# Blattdurchmesser.net
KiCad netlist of a schematic drawn in EAGLE
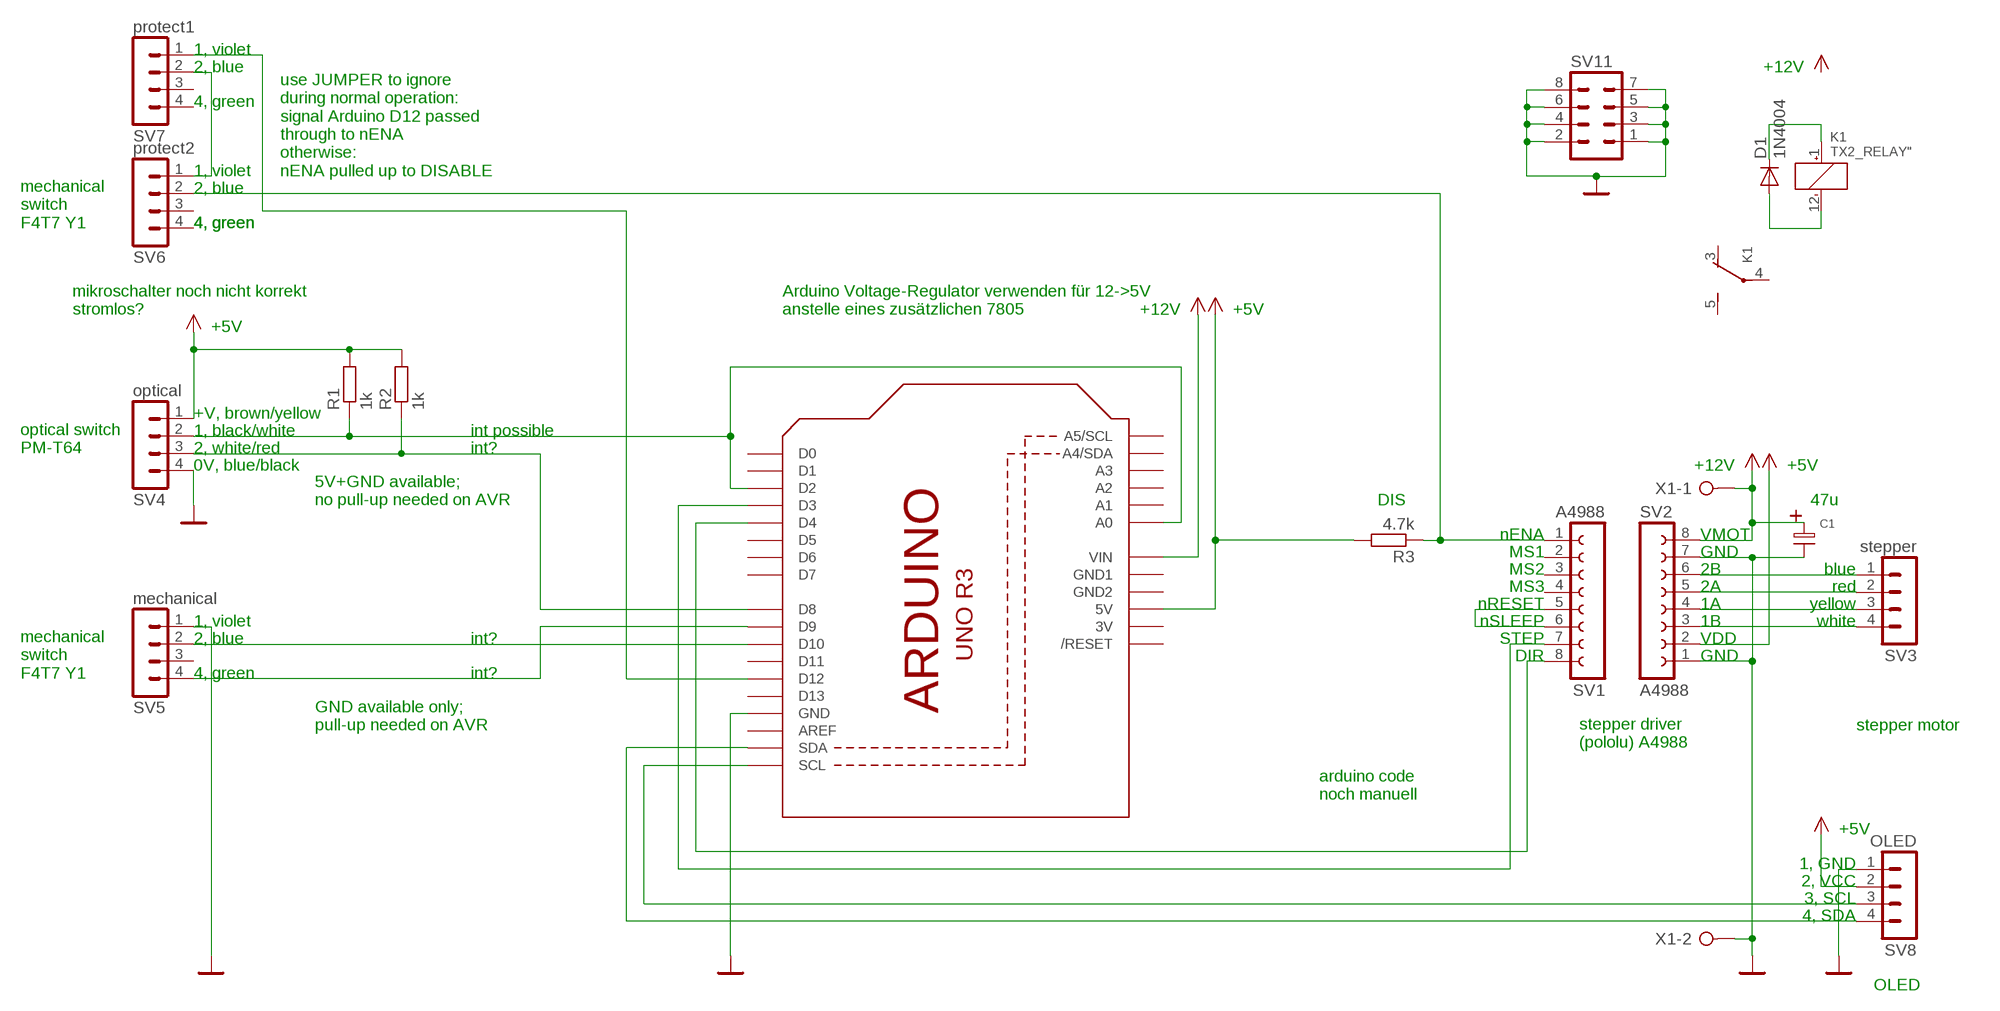
[diagram p0: schematic, sheet 1]

(export (version "E")
  (design (tool "Eeschema 10.0.6"))
  (components
    (comp (ref "C1")
      (value "R_ELKO_8.1")
      (footprint "eagle-import:R_ELK_8.1")
      (libsource (lib "eagle-import") (part "R_ELKO_8.1"))
    )
    (comp (ref "D1")
      (value "1N4004")
      (footprint "eagle-import:DO41-10")
      (libsource (lib "eagle-import") (part "1N4004"))
    )
    (comp (ref "K1")
      (value "TX2_RELAY\"")
      (footprint "eagle-import:TX2")
      (libsource (lib "eagle-import") (part "TX2_RELAY{dblquote}"))
    )
    (comp (ref "Q1")
      (value "ARDUINOR3-NOIOREF-NOTEXT")
      (footprint "eagle-import:ARDUINOR3-NOTEXT-NOIOREF")
      (libsource (lib "eagle-import") (part "ARDUINOR3-NOIOREF-NOTEXT"))
    )
    (comp (ref "R1")
      (value "1k")
      (footprint "eagle-import:0207_10")
      (libsource (lib "eagle-import") (part "R-EU_0207/10"))
    )
    (comp (ref "R2")
      (value "1k")
      (footprint "eagle-import:0207_10")
      (libsource (lib "eagle-import") (part "R-EU_0207/10"))
    )
    (comp (ref "R3")
      (value "4.7k")
      (footprint "eagle-import:0207_10")
      (libsource (lib "eagle-import") (part "R-EU_0207/10"))
    )
    (comp (ref "SV1")
      (value "A4988")
      (footprint "eagle-import:FE08")
      (libsource (lib "eagle-import") (part "FE08-1"))
    )
    (comp (ref "SV2")
      (value "A4988")
      (footprint "eagle-import:FE08")
      (libsource (lib "eagle-import") (part "FE08-1"))
    )
    (comp (ref "SV3")
      (value "stepper")
      (footprint "eagle-import:MA04-1")
      (libsource (lib "eagle-import") (part "MA04-1"))
    )
    (comp (ref "SV4")
      (value "optical")
      (footprint "eagle-import:MA04-1")
      (libsource (lib "eagle-import") (part "MA04-1"))
    )
    (comp (ref "SV5")
      (value "mechanical")
      (footprint "eagle-import:MA04-1")
      (libsource (lib "eagle-import") (part "MA04-1"))
    )
    (comp (ref "SV6")
      (value "protect2")
      (footprint "eagle-import:MA04-1")
      (libsource (lib "eagle-import") (part "MA04-1"))
    )
    (comp (ref "SV7")
      (value "protect1")
      (footprint "eagle-import:MA04-1")
      (libsource (lib "eagle-import") (part "MA04-1"))
    )
    (comp (ref "SV8")
      (value "OLED")
      (footprint "eagle-import:MA04-1")
      (libsource (lib "eagle-import") (part "MA04-1"))
    )
    (comp (ref "SV11")
      (value "MA04-2")
      (footprint "eagle-import:MA04-2")
      (libsource (lib "eagle-import") (part "MA04-2"))
    )
    (comp (ref "X1")
      (value "W237-02P")
      (footprint "eagle-import:W237-132")
      (libsource (lib "eagle-import") (part "W237-02P"))
    )
  )
  (nets
    (net (code "1") (name "+5V") (class "Default")
      (node (ref "Q1") (pin "5V") (pinfunction "5V_5V") (pintype "power_in"))
      (node (ref "R1") (pin "2") (pinfunction "2_2") (pintype "passive"))
      (node (ref "R2") (pin "2") (pinfunction "2_2") (pintype "passive"))
      (node (ref "R3") (pin "2") (pinfunction "2_2") (pintype "passive"))
      (node (ref "SV2") (pin "2") (pinfunction "2_2") (pintype "passive"))
      (node (ref "SV4") (pin "1") (pinfunction "1_1") (pintype "passive"))
      (node (ref "SV8") (pin "2") (pinfunction "2_2") (pintype "passive"))
    )
    (net (code "2") (name "+12V") (class "Default")
      (node (ref "C1") (pin "P") (pinfunction "P_P") (pintype "passive"))
      (node (ref "Q1") (pin "VIN") (pinfunction "VIN_VIN") (pintype "power_in"))
      (node (ref "SV2") (pin "8") (pinfunction "8_8") (pintype "passive"))
      (node (ref "X1") (pin "1") (pinfunction "KL_1") (pintype "passive"))
    )
    (net (code "3") (name "/3V") (class "Default")
      (node (ref "Q1") (pin "3V") (pinfunction "3V_3V") (pintype "power_in"))
    )
    (net (code "4") (name "/GND1") (class "Default")
      (node (ref "Q1") (pin "GND1") (pinfunction "GND1_GND1") (pintype "power_in"))
    )
    (net (code "5") (name "/GND2") (class "Default")
      (node (ref "Q1") (pin "GND2") (pinfunction "GND2_GND2") (pintype "power_in"))
    )
    (net (code "6") (name "GND") (class "Default")
      (node (ref "C1") (pin "N") (pinfunction "N_N") (pintype "passive"))
      (node (ref "Q1") (pin "GND") (pinfunction "GND_GND") (pintype "power_in"))
      (node (ref "SV11") (pin "1") (pinfunction "1_1") (pintype "passive"))
      (node (ref "SV11") (pin "2") (pinfunction "2_2") (pintype "passive"))
      (node (ref "SV11") (pin "3") (pinfunction "3_3") (pintype "passive"))
      (node (ref "SV11") (pin "4") (pinfunction "4_4") (pintype "passive"))
      (node (ref "SV11") (pin "5") (pinfunction "5_5") (pintype "passive"))
      (node (ref "SV11") (pin "6") (pinfunction "6_6") (pintype "passive"))
      (node (ref "SV11") (pin "7") (pinfunction "7_7") (pintype "passive"))
      (node (ref "SV11") (pin "8") (pinfunction "8_8") (pintype "passive"))
      (node (ref "SV2") (pin "1") (pinfunction "1_1") (pintype "passive"))
      (node (ref "SV2") (pin "7") (pinfunction "7_7") (pintype "passive"))
      (node (ref "SV4") (pin "4") (pinfunction "4_4") (pintype "passive"))
      (node (ref "SV5") (pin "1") (pinfunction "1_1") (pintype "passive"))
      (node (ref "SV8") (pin "1") (pinfunction "1_1") (pintype "passive"))
      (node (ref "X1") (pin "2") (pinfunction "KL_2") (pintype "passive"))
    )
    (net (code "7") (name "Net-(K1A-+)") (class "Default")
      (node (ref "D1") (pin "C") (pinfunction "C_C") (pintype "passive"))
      (node (ref "K1") (pin "1") (pinfunction "+_1") (pintype "passive"))
    )
    (net (code "8") (name "Net-(K1A--)") (class "Default")
      (node (ref "D1") (pin "A") (pinfunction "A_A") (pintype "passive"))
      (node (ref "K1") (pin "12") (pinfunction "-_12") (pintype "passive"))
    )
    (net (code "9") (name "Net-(Q1-PadA0)") (class "Default")
      (node (ref "Q1") (pin "A0") (pinfunction "A0_A0") (pintype "bidirectional"))
      (node (ref "Q1") (pin "D2") (pinfunction "D2_D2") (pintype "bidirectional"))
      (node (ref "R1") (pin "1") (pinfunction "1_1") (pintype "passive"))
      (node (ref "SV4") (pin "2") (pinfunction "2_2") (pintype "passive"))
    )
    (net (code "10") (name "Net-(Q1-PadD3)") (class "Default")
      (node (ref "Q1") (pin "D3") (pinfunction "D3_D3") (pintype "bidirectional"))
      (node (ref "SV1") (pin "7") (pinfunction "7_7") (pintype "passive"))
    )
    (net (code "11") (name "Net-(Q1-PadD4)") (class "Default")
      (node (ref "Q1") (pin "D4") (pinfunction "D4_D4") (pintype "bidirectional"))
      (node (ref "SV1") (pin "8") (pinfunction "8_8") (pintype "passive"))
    )
    (net (code "12") (name "Net-(Q1-PadD8)") (class "Default")
      (node (ref "Q1") (pin "D8") (pinfunction "D8_D8") (pintype "bidirectional"))
      (node (ref "R2") (pin "1") (pinfunction "1_1") (pintype "passive"))
      (node (ref "SV4") (pin "3") (pinfunction "3_3") (pintype "passive"))
    )
    (net (code "13") (name "Net-(Q1-PadD9)") (class "Default")
      (node (ref "Q1") (pin "D9") (pinfunction "D9_D9") (pintype "bidirectional"))
      (node (ref "SV5") (pin "4") (pinfunction "4_4") (pintype "passive"))
    )
    (net (code "14") (name "Net-(Q1-PadD10)") (class "Default")
      (node (ref "Q1") (pin "D10") (pinfunction "D10_D10") (pintype "bidirectional"))
      (node (ref "SV5") (pin "2") (pinfunction "2_2") (pintype "passive"))
    )
    (net (code "15") (name "Net-(Q1-PadD12)") (class "Default")
      (node (ref "Q1") (pin "D12") (pinfunction "D12_D12") (pintype "bidirectional"))
      (node (ref "SV7") (pin "1") (pinfunction "1_1") (pintype "passive"))
    )
    (net (code "16") (name "Net-(Q1-PadSCL)") (class "Default")
      (node (ref "Q1") (pin "SCL") (pinfunction "SCL_SCL") (pintype "bidirectional"))
      (node (ref "SV8") (pin "3") (pinfunction "3_3") (pintype "passive"))
    )
    (net (code "17") (name "Net-(Q1-PadSDA)") (class "Default")
      (node (ref "Q1") (pin "SDA") (pinfunction "SDA_SDA") (pintype "bidirectional"))
      (node (ref "SV8") (pin "4") (pinfunction "4_4") (pintype "passive"))
    )
    (net (code "18") (name "Net-(R3-Pad1)") (class "Default")
      (node (ref "R3") (pin "1") (pinfunction "1_1") (pintype "passive"))
      (node (ref "SV1") (pin "1") (pinfunction "1_1") (pintype "passive"))
      (node (ref "SV6") (pin "2") (pinfunction "2_2") (pintype "passive"))
    )
    (net (code "19") (name "Net-(SV1-Pad5)") (class "Default")
      (node (ref "SV1") (pin "5") (pinfunction "5_5") (pintype "passive"))
      (node (ref "SV1") (pin "6") (pinfunction "6_6") (pintype "passive"))
    )
    (net (code "20") (name "Net-(SV2-Pad3)") (class "Default")
      (node (ref "SV2") (pin "3") (pinfunction "3_3") (pintype "passive"))
      (node (ref "SV3") (pin "4") (pinfunction "4_4") (pintype "passive"))
    )
    (net (code "21") (name "Net-(SV2-Pad4)") (class "Default")
      (node (ref "SV2") (pin "4") (pinfunction "4_4") (pintype "passive"))
      (node (ref "SV3") (pin "3") (pinfunction "3_3") (pintype "passive"))
    )
    (net (code "22") (name "Net-(SV2-Pad5)") (class "Default")
      (node (ref "SV2") (pin "5") (pinfunction "5_5") (pintype "passive"))
      (node (ref "SV3") (pin "2") (pinfunction "2_2") (pintype "passive"))
    )
    (net (code "23") (name "Net-(SV2-Pad6)") (class "Default")
      (node (ref "SV2") (pin "6") (pinfunction "6_6") (pintype "passive"))
      (node (ref "SV3") (pin "1") (pinfunction "1_1") (pintype "passive"))
    )
    (net (code "24") (name "Net-(SV6-Pad1)") (class "Default")
      (node (ref "SV6") (pin "1") (pinfunction "1_1") (pintype "passive"))
      (node (ref "SV7") (pin "2") (pinfunction "2_2") (pintype "passive"))
    )
    (net (code "25") (name "unconnected-(K1B-O-Pad3)") (class "Default")
      (node (ref "K1") (pin "3") (pinfunction "O_3") (pintype "passive"))
    )
    (net (code "26") (name "unconnected-(K1B-P-Pad4)") (class "Default")
      (node (ref "K1") (pin "4") (pinfunction "P_4") (pintype "passive"))
    )
    (net (code "27") (name "unconnected-(K1B-S-Pad5)") (class "Default")
      (node (ref "K1") (pin "5") (pinfunction "S_5") (pintype "passive"))
    )
    (net (code "28") (name "unconnected-(Q1-A4{slash}SDA-PadA4)") (class "Default")
      (node (ref "Q1") (pin "A4") (pinfunction "A4/SDA_A4") (pintype "bidirectional"))
    )
    (net (code "29") (name "unconnected-(Q1-A5{slash}SCL-PadA5)") (class "Default")
      (node (ref "Q1") (pin "A5") (pinfunction "A5/SCL_A5") (pintype "bidirectional"))
    )
    (net (code "30") (name "unconnected-(Q1-PadA1)") (class "Default")
      (node (ref "Q1") (pin "A1") (pinfunction "A1_A1") (pintype "bidirectional"))
    )
    (net (code "31") (name "unconnected-(Q1-PadA2)") (class "Default")
      (node (ref "Q1") (pin "A2") (pinfunction "A2_A2") (pintype "bidirectional"))
    )
    (net (code "32") (name "unconnected-(Q1-PadA3)") (class "Default")
      (node (ref "Q1") (pin "A3") (pinfunction "A3_A3") (pintype "bidirectional"))
    )
    (net (code "33") (name "unconnected-(Q1-PadAREF)") (class "Default")
      (node (ref "Q1") (pin "AREF") (pinfunction "AREF_AREF") (pintype "bidirectional"))
    )
    (net (code "34") (name "unconnected-(Q1-PadD0)") (class "Default")
      (node (ref "Q1") (pin "D0") (pinfunction "D0_D0") (pintype "bidirectional"))
    )
    (net (code "35") (name "unconnected-(Q1-PadD1)") (class "Default")
      (node (ref "Q1") (pin "D1") (pinfunction "D1_D1") (pintype "bidirectional"))
    )
    (net (code "36") (name "unconnected-(Q1-PadD5)") (class "Default")
      (node (ref "Q1") (pin "D5") (pinfunction "D5_D5") (pintype "bidirectional"))
    )
    (net (code "37") (name "unconnected-(Q1-PadD6)") (class "Default")
      (node (ref "Q1") (pin "D6") (pinfunction "D6_D6") (pintype "bidirectional"))
    )
    (net (code "38") (name "unconnected-(Q1-PadD7)") (class "Default")
      (node (ref "Q1") (pin "D7") (pinfunction "D7_D7") (pintype "bidirectional"))
    )
    (net (code "39") (name "unconnected-(Q1-PadD11)") (class "Default")
      (node (ref "Q1") (pin "D11") (pinfunction "D11_D11") (pintype "bidirectional"))
    )
    (net (code "40") (name "unconnected-(Q1-PadD13)") (class "Default")
      (node (ref "Q1") (pin "D13") (pinfunction "D13_D13") (pintype "bidirectional"))
    )
    (net (code "41") (name "unconnected-(Q1-{slash}RESET-PadRESET)") (class "Default")
      (node (ref "Q1") (pin "RESET") (pinfunction "/RESET_RESET") (pintype "bidirectional"))
    )
    (net (code "42") (name "unconnected-(SV1-Pad2)") (class "Default")
      (node (ref "SV1") (pin "2") (pinfunction "2_2") (pintype "passive"))
    )
    (net (code "43") (name "unconnected-(SV1-Pad3)") (class "Default")
      (node (ref "SV1") (pin "3") (pinfunction "3_3") (pintype "passive"))
    )
    (net (code "44") (name "unconnected-(SV1-Pad4)") (class "Default")
      (node (ref "SV1") (pin "4") (pinfunction "4_4") (pintype "passive"))
    )
    (net (code "45") (name "unconnected-(SV5-Pad3)") (class "Default")
      (node (ref "SV5") (pin "3") (pinfunction "3_3") (pintype "passive"))
    )
    (net (code "46") (name "unconnected-(SV6-Pad3)") (class "Default")
      (node (ref "SV6") (pin "3") (pinfunction "3_3") (pintype "passive"))
    )
    (net (code "47") (name "unconnected-(SV6-Pad4)") (class "Default")
      (node (ref "SV6") (pin "4") (pinfunction "4_4") (pintype "passive"))
    )
    (net (code "48") (name "unconnected-(SV7-Pad3)") (class "Default")
      (node (ref "SV7") (pin "3") (pinfunction "3_3") (pintype "passive"))
    )
    (net (code "49") (name "unconnected-(SV7-Pad4)") (class "Default")
      (node (ref "SV7") (pin "4") (pinfunction "4_4") (pintype "passive"))
    )
  )
)
